# Comm_Log.net
KiCad netlist of a schematic drawn in EAGLE
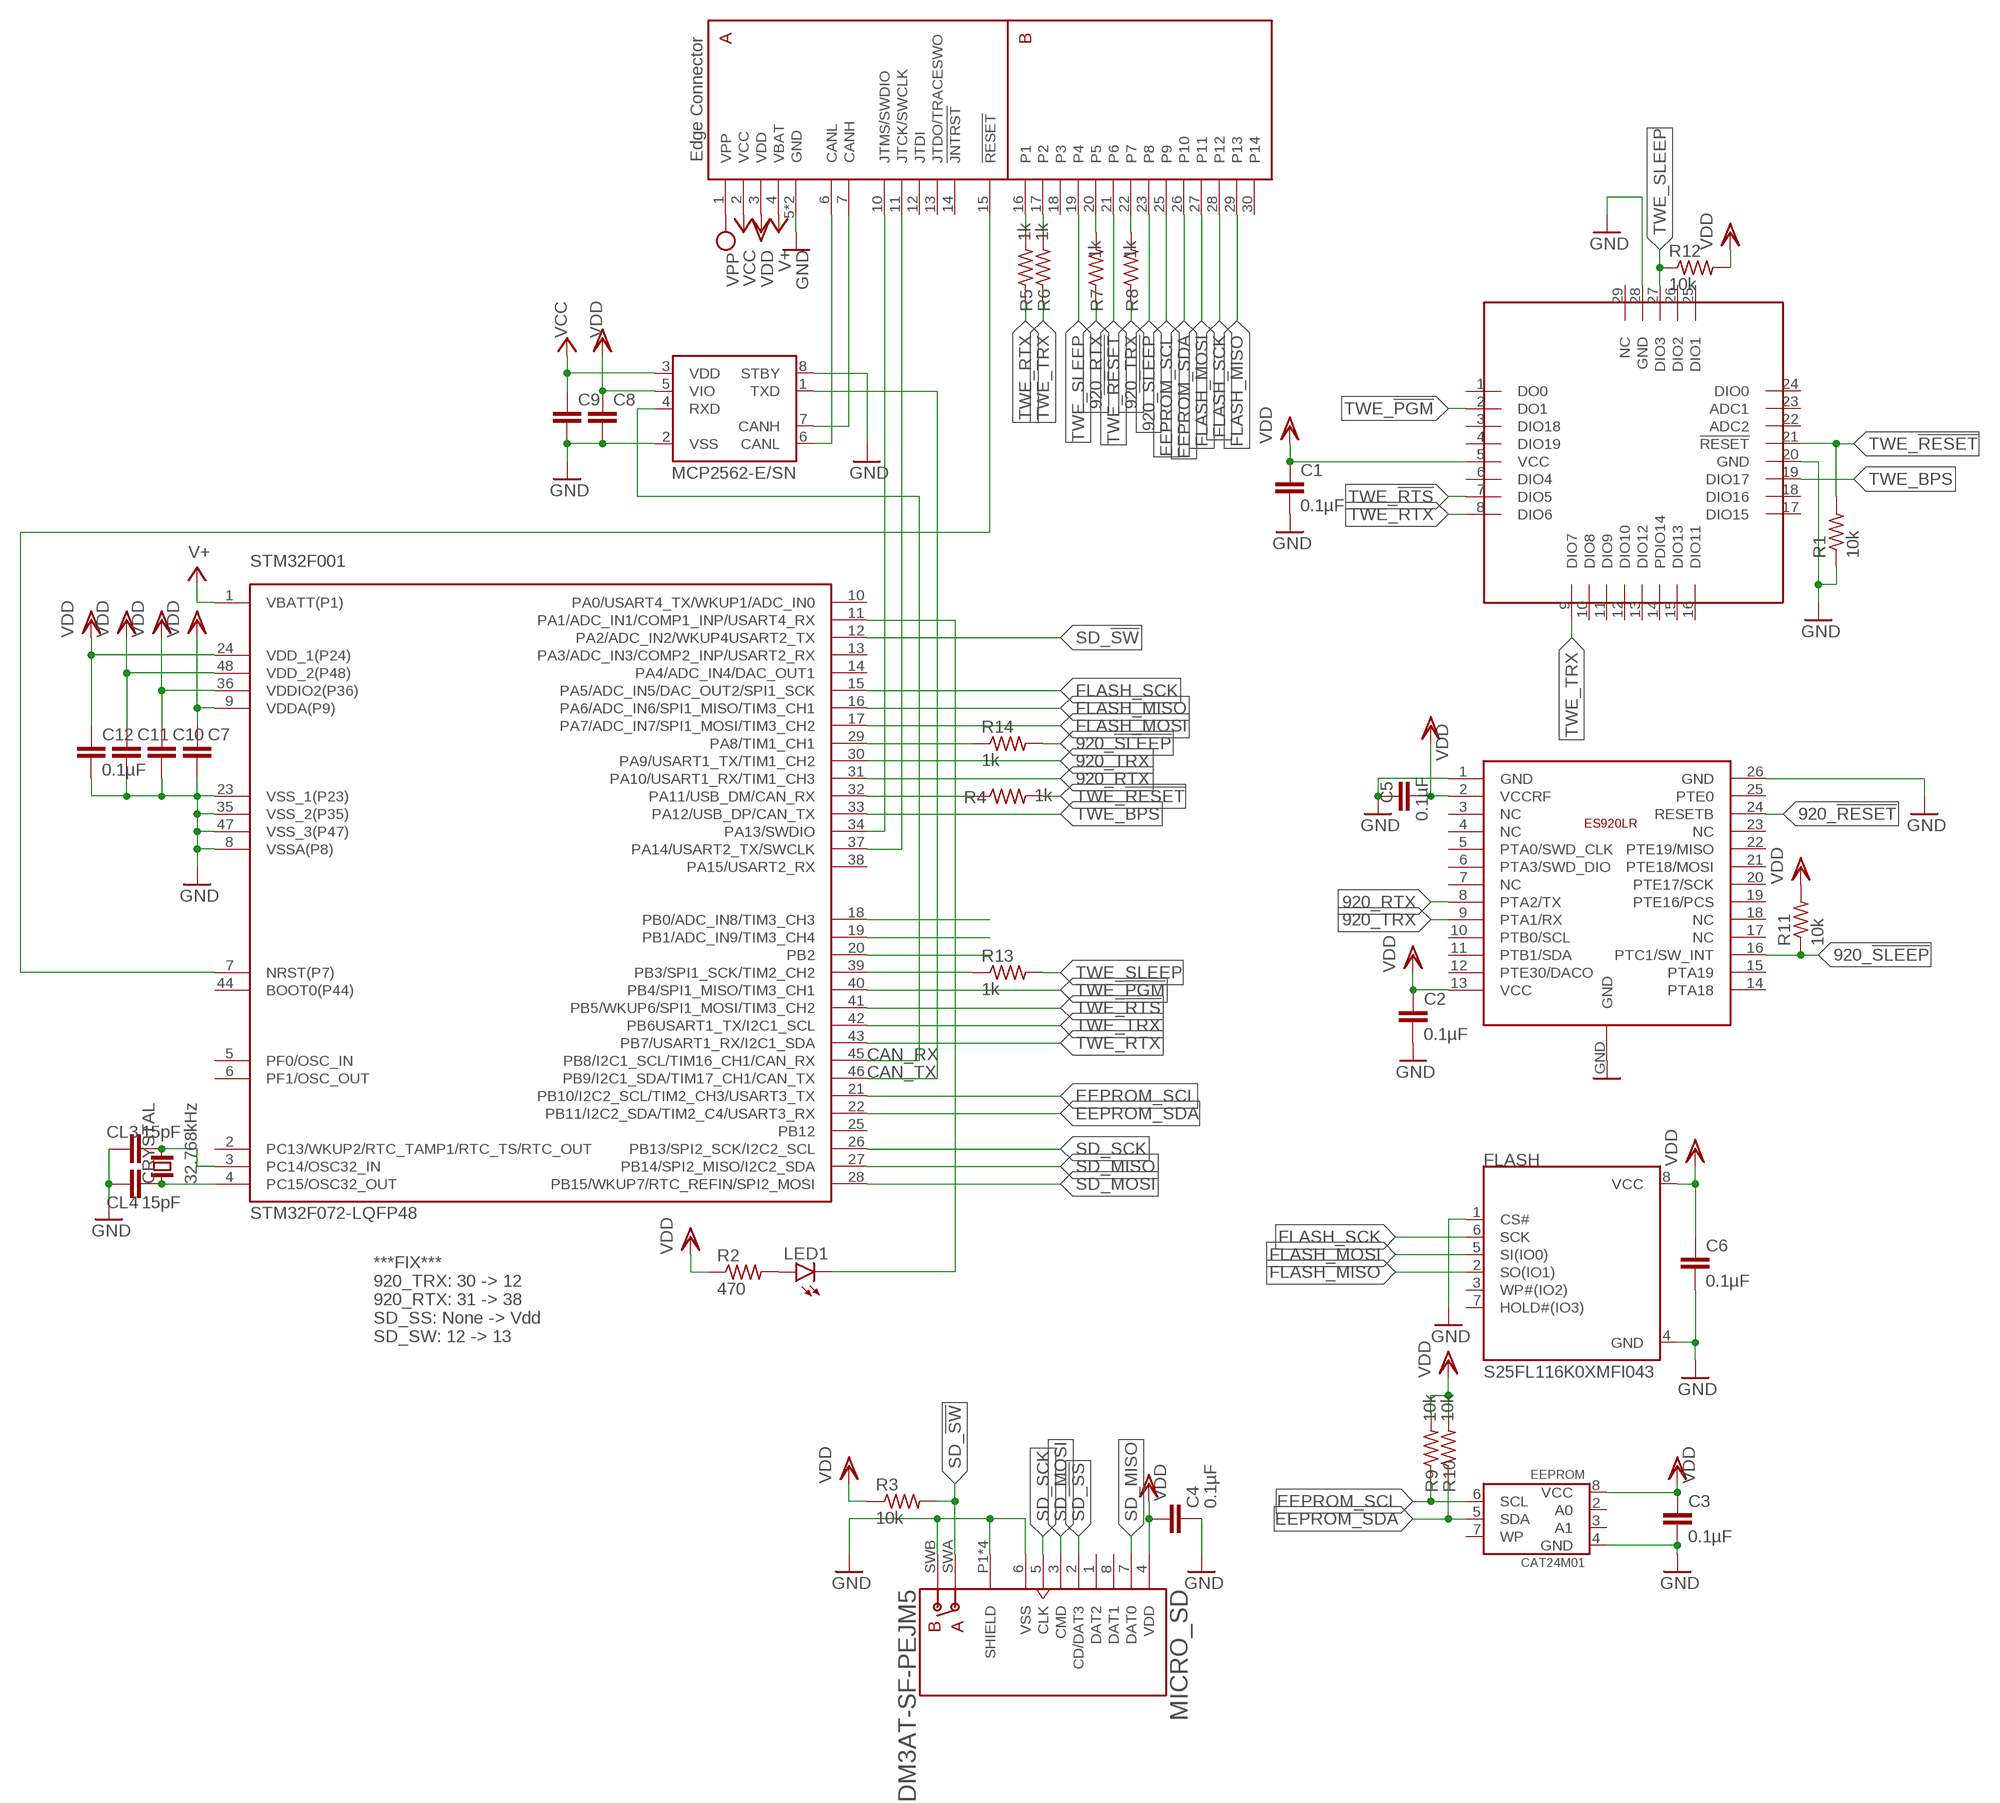
[diagram p0: schematic, sheet 1]

(export (version "E")
  (design (tool "Eeschema 10.0.6"))
  (components
    (comp (ref "C1")
      (value "0.1µF")
      (footprint "eagle-import:C0603K")
      (libsource (lib "eagle-import") (part "C-EUC0603K"))
    )
    (comp (ref "C2")
      (value "0.1µF")
      (footprint "eagle-import:C0603K")
      (libsource (lib "eagle-import") (part "C-EUC0603K"))
    )
    (comp (ref "C3")
      (value "0.1µF")
      (footprint "eagle-import:C0603K")
      (libsource (lib "eagle-import") (part "C-EUC0603K"))
    )
    (comp (ref "C4")
      (value "0.1µF")
      (footprint "eagle-import:C0603K")
      (libsource (lib "eagle-import") (part "C-EUC0603K"))
    )
    (comp (ref "C5")
      (value "0.1µF")
      (footprint "eagle-import:C0603K")
      (libsource (lib "eagle-import") (part "C-EUC0603K"))
    )
    (comp (ref "C6")
      (value "0.1µF")
      (footprint "eagle-import:C0603K")
      (libsource (lib "eagle-import") (part "C-EUC0603K"))
    )
    (comp (ref "C7")
      (value "C-EUC0603K")
      (footprint "eagle-import:C0603K")
      (libsource (lib "eagle-import") (part "C-EUC0603K"))
    )
    (comp (ref "C8")
      (value "C-EUC0603K")
      (footprint "eagle-import:C0603K")
      (libsource (lib "eagle-import") (part "C-EUC0603K"))
    )
    (comp (ref "C9")
      (value "C-EUC0603K")
      (footprint "eagle-import:C0603K")
      (libsource (lib "eagle-import") (part "C-EUC0603K"))
    )
    (comp (ref "C10")
      (value "C-EUC0603K")
      (footprint "eagle-import:C0603K")
      (libsource (lib "eagle-import") (part "C-EUC0603K"))
    )
    (comp (ref "C11")
      (value "C-EUC0603K")
      (footprint "eagle-import:C0603K")
      (libsource (lib "eagle-import") (part "C-EUC0603K"))
    )
    (comp (ref "C12")
      (value "0.1µF")
      (footprint "eagle-import:C0603K")
      (libsource (lib "eagle-import") (part "C-EUC0603K"))
    )
    (comp (ref "CL3")
      (value "15pF")
      (footprint "eagle-import:C0603K")
      (libsource (lib "eagle-import") (part "C-EUC0603K"))
    )
    (comp (ref "CL4")
      (value "15pF")
      (footprint "eagle-import:C0603K")
      (libsource (lib "eagle-import") (part "C-EUC0603K"))
    )
    (comp (ref "CRYSTAL")
      (value "32.768kHz")
      (footprint "eagle-import:FC-255")
      (libsource (lib "eagle-import") (part "CRYTALFC-255"))
    )
    (comp (ref "EEPROM")
      (value "CAT24M01")
      (footprint "eagle-import:SO-8")
      (fields (field (name "MF") "ON Semiconductor"))
      (libsource (lib "eagle-import") (part "CAT24M01"))
    )
    (comp (ref "ES920LR")
      (value "ES920LR")
      (footprint "eagle-import:ES920LR")
      (libsource (lib "eagle-import") (part "ES920LR"))
    )
    (comp (ref "FLASH")
      (value "S25FL116K0XMFI043")
      (footprint "eagle-import:SOIC127P600X175-8N")
      (fields (field (name "MF") "Cypress Semiconductor"))
      (libsource (lib "eagle-import") (part "S25FL116K0XMFI043"))
    )
    (comp (ref "LED1")
      (value "LEDCHIP-LED0603")
      (footprint "eagle-import:CHIP-LED0603")
      (libsource (lib "eagle-import") (part "LEDCHIP-LED0603"))
    )
    (comp (ref "MCP1")
      (value "MCP2562-E/SN")
      (footprint "eagle-import:SOIC127P600X175-8N")
      (fields (field (name "MF") "Microchip"))
      (libsource (lib "eagle-import") (part "MCP2562-E/SN"))
    )
    (comp (ref "MICRO_SD")
      (value "DM3AT-SF-PEJM5")
      (footprint "eagle-import:HRS_DM3AT-SF-PEJM5")
      (fields (field (name "DIGI-KEY_PART_NUMBER") "HR1964CT-ND") (field (name "MF") "Hirose"))
      (libsource (lib "eagle-import") (part "DM3AT-SF-PEJM5"))
    )
    (comp (ref "R1")
      (value "10k")
      (footprint "eagle-import:R0603")
      (libsource (lib "eagle-import") (part "R-US_R0603"))
    )
    (comp (ref "R2")
      (value "470")
      (footprint "eagle-import:R0603")
      (libsource (lib "eagle-import") (part "R-US_R0603"))
    )
    (comp (ref "R3")
      (value "10k")
      (footprint "eagle-import:R0603")
      (libsource (lib "eagle-import") (part "R-US_R0603"))
    )
    (comp (ref "R4")
      (value "1k")
      (footprint "eagle-import:R0603")
      (libsource (lib "eagle-import") (part "R-US_R0603"))
    )
    (comp (ref "R5")
      (value "1k")
      (footprint "eagle-import:R0603")
      (libsource (lib "eagle-import") (part "R-US_R0603"))
    )
    (comp (ref "R6")
      (value "1k")
      (footprint "eagle-import:R0603")
      (libsource (lib "eagle-import") (part "R-US_R0603"))
    )
    (comp (ref "R7")
      (value "1k")
      (footprint "eagle-import:R0603")
      (libsource (lib "eagle-import") (part "R-US_R0603"))
    )
    (comp (ref "R8")
      (value "1k")
      (footprint "eagle-import:R0603")
      (libsource (lib "eagle-import") (part "R-US_R0603"))
    )
    (comp (ref "R9")
      (value "10k")
      (footprint "eagle-import:R0603")
      (libsource (lib "eagle-import") (part "resistor_348_R-US_R0603"))
    )
    (comp (ref "R10")
      (value "10k")
      (footprint "eagle-import:R0603")
      (libsource (lib "eagle-import") (part "resistor_348_R-US_R0603"))
    )
    (comp (ref "R11")
      (value "10k")
      (footprint "eagle-import:R0603")
      (libsource (lib "eagle-import") (part "resistor_348_R-US_R0603"))
    )
    (comp (ref "R12")
      (value "10k")
      (footprint "eagle-import:R0603")
      (libsource (lib "eagle-import") (part "resistor_348_R-US_R0603"))
    )
    (comp (ref "R13")
      (value "1k")
      (footprint "eagle-import:R0603")
      (libsource (lib "eagle-import") (part "resistor_348_R-US_R0603"))
    )
    (comp (ref "R14")
      (value "1k")
      (footprint "eagle-import:R0603")
      (libsource (lib "eagle-import") (part "resistor_348_R-US_R0603"))
    )
    (comp (ref "STM32F001")
      (value "STM32F072-LQFP48")
      (footprint "eagle-import:LQFP48")
      (libsource (lib "eagle-import") (part "STM32F072-LQFP48"))
    )
    (comp (ref "TWE-LITE")
      (value "LITE")
      (footprint "eagle-import:LITE")
      (libsource (lib "eagle-import") (part "LITE"))
    )
    (comp (ref "U$2")
      (value "EDGE30")
      (footprint "eagle-import:EDGE30")
      (libsource (lib "eagle-import") (part "EDGE30"))
    )
  )
  (nets
    (net (code "1") (name "/920_~{RESET}") (class "Default")
      (node (ref "ES920LR") (pin "24") (pinfunction "RESETB_24") (pintype "bidirectional"))
    )
    (net (code "2") (name "/920_~{SLEEP}") (class "Default")
      (node (ref "ES920LR") (pin "16") (pinfunction "PTC1/SW_INT_16") (pintype "bidirectional"))
      (node (ref "R11") (pin "1") (pinfunction "1_1") (pintype "passive"))
      (node (ref "R14") (pin "2") (pinfunction "2_2") (pintype "passive"))
      (node (ref "U$2") (pin "23") (pinfunction "P8_23") (pintype "bidirectional"))
    )
    (net (code "3") (name "/CAN_RX") (class "Default")
      (node (ref "MCP1") (pin "4") (pinfunction "RXD_4") (pintype "output"))
      (node (ref "STM32F001") (pin "45") (pinfunction "PB8/I2C1_SCL/TIM16_CH1/CAN_RX_45") (pintype "bidirectional"))
    )
    (net (code "4") (name "/CAN_TX") (class "Default")
      (node (ref "MCP1") (pin "1") (pinfunction "TXD_1") (pintype "input"))
      (node (ref "STM32F001") (pin "46") (pinfunction "PB9/I2C1_SDA/TIM17_CH1/CAN_TX_46") (pintype "bidirectional"))
    )
    (net (code "5") (name "/SD_~{SS}") (class "Default")
      (node (ref "MICRO_SD") (pin "2") (pinfunction "CD/DAT3_2") (pintype "bidirectional"))
    )
    (net (code "6") (name "/SD_~{SW}") (class "Default")
      (node (ref "MICRO_SD") (pin "SWA") (pinfunction "A_SWA") (pintype "bidirectional"))
      (node (ref "R3") (pin "2") (pinfunction "2_2") (pintype "passive"))
      (node (ref "STM32F001") (pin "12") (pinfunction "PA2/ADC_IN2/WKUP4USART2_TX_12") (pintype "bidirectional"))
    )
    (net (code "7") (name "/TWE_~{PGM}") (class "Default")
      (node (ref "STM32F001") (pin "40") (pinfunction "PB4/SPI1_MISO/TIM3_CH1_40") (pintype "bidirectional"))
      (node (ref "TWE-LITE") (pin "2") (pinfunction "DO1_2") (pintype "bidirectional"))
    )
    (net (code "8") (name "/TWE_~{RESET}") (class "Default")
      (node (ref "R1") (pin "2") (pinfunction "2_2") (pintype "passive"))
      (node (ref "R4") (pin "2") (pinfunction "2_2") (pintype "passive"))
      (node (ref "TWE-LITE") (pin "21") (pinfunction "~{RESET}_21") (pintype "input"))
      (node (ref "U$2") (pin "21") (pinfunction "P6_21") (pintype "bidirectional"))
    )
    (net (code "9") (name "/TWE_~{RTS}") (class "Default")
      (node (ref "STM32F001") (pin "41") (pinfunction "PB5/WKUP6/SPI1_MOSI/TIM3_CH2_41") (pintype "bidirectional"))
      (node (ref "TWE-LITE") (pin "7") (pinfunction "DIO5_7") (pintype "bidirectional"))
    )
    (net (code "10") (name "920_RTX") (class "Default")
      (node (ref "ES920LR") (pin "8") (pinfunction "PTA2/TX_8") (pintype "bidirectional"))
      (node (ref "R7") (pin "1") (pinfunction "1_1") (pintype "passive"))
      (node (ref "STM32F001") (pin "31") (pinfunction "PA10/USART1_RX/TIM1_CH3_31") (pintype "bidirectional"))
    )
    (net (code "11") (name "920_TRX") (class "Default")
      (node (ref "ES920LR") (pin "9") (pinfunction "PTA1/RX_9") (pintype "bidirectional"))
      (node (ref "R8") (pin "1") (pinfunction "1_1") (pintype "passive"))
      (node (ref "STM32F001") (pin "30") (pinfunction "PA9/USART1_TX/TIM1_CH2_30") (pintype "bidirectional"))
    )
    (net (code "12") (name "EEPROM_SCL") (class "Default")
      (node (ref "EEPROM") (pin "6") (pinfunction "SCL_6") (pintype "bidirectional"))
      (node (ref "R9") (pin "1") (pinfunction "1_1") (pintype "passive"))
      (node (ref "STM32F001") (pin "21") (pinfunction "PB10/I2C2_SCL/TIM2_CH3/USART3_TX_21") (pintype "bidirectional"))
      (node (ref "U$2") (pin "25") (pinfunction "P9_25") (pintype "bidirectional"))
    )
    (net (code "13") (name "EEPROM_SDA") (class "Default")
      (node (ref "EEPROM") (pin "5") (pinfunction "SDA_5") (pintype "bidirectional"))
      (node (ref "R10") (pin "1") (pinfunction "1_1") (pintype "passive"))
      (node (ref "STM32F001") (pin "22") (pinfunction "PB11/I2C2_SDA/TIM2_C4/USART3_RX_22") (pintype "bidirectional"))
      (node (ref "U$2") (pin "26") (pinfunction "P10_26") (pintype "bidirectional"))
    )
    (net (code "14") (name "FLASH_MISO") (class "Default")
      (node (ref "FLASH") (pin "2") (pinfunction "SO(IO1)_2") (pintype "bidirectional"))
      (node (ref "STM32F001") (pin "16") (pinfunction "PA6/ADC_IN6/SPI1_MISO/TIM3_CH1_16") (pintype "bidirectional"))
      (node (ref "U$2") (pin "29") (pinfunction "P13_29") (pintype "bidirectional"))
    )
    (net (code "15") (name "FLASH_MOSI") (class "Default")
      (node (ref "FLASH") (pin "5") (pinfunction "SI(IO0)_5") (pintype "bidirectional"))
      (node (ref "STM32F001") (pin "17") (pinfunction "PA7/ADC_IN7/SPI1_MOSI/TIM3_CH2_17") (pintype "bidirectional"))
      (node (ref "U$2") (pin "27") (pinfunction "P11_27") (pintype "bidirectional"))
    )
    (net (code "16") (name "FLASH_SCK") (class "Default")
      (node (ref "FLASH") (pin "6") (pinfunction "SCK_6") (pintype "input"))
      (node (ref "STM32F001") (pin "15") (pinfunction "PA5/ADC_IN5/DAC_OUT2/SPI1_SCK_15") (pintype "bidirectional"))
      (node (ref "U$2") (pin "28") (pinfunction "P12_28") (pintype "bidirectional"))
    )
    (net (code "17") (name "GND") (class "Default")
      (node (ref "C1") (pin "2") (pinfunction "2_2") (pintype "passive"))
      (node (ref "C10") (pin "2") (pinfunction "2_2") (pintype "passive"))
      (node (ref "C11") (pin "2") (pinfunction "2_2") (pintype "passive"))
      (node (ref "C12") (pin "2") (pinfunction "2_2") (pintype "passive"))
      (node (ref "C2") (pin "2") (pinfunction "2_2") (pintype "passive"))
      (node (ref "C3") (pin "2") (pinfunction "2_2") (pintype "passive"))
      (node (ref "C4") (pin "2") (pinfunction "2_2") (pintype "passive"))
      (node (ref "C5") (pin "1") (pinfunction "1_1") (pintype "passive"))
      (node (ref "C6") (pin "2") (pinfunction "2_2") (pintype "passive"))
      (node (ref "C7") (pin "2") (pinfunction "2_2") (pintype "passive"))
      (node (ref "C8") (pin "2") (pinfunction "2_2") (pintype "passive"))
      (node (ref "C9") (pin "2") (pinfunction "2_2") (pintype "passive"))
      (node (ref "CL3") (pin "1") (pinfunction "1_1") (pintype "passive"))
      (node (ref "CL4") (pin "1") (pinfunction "1_1") (pintype "passive"))
      (node (ref "EEPROM") (pin "4") (pinfunction "GND_4") (pintype "bidirectional"))
      (node (ref "ES920LR") (pin "1") (pinfunction "GND_1") (pintype "bidirectional"))
      (node (ref "ES920LR") (pin "26") (pinfunction "GND_26") (pintype "bidirectional"))
      (node (ref "ES920LR") (pin "GND") (pinfunction "GND_GND") (pintype "bidirectional"))
      (node (ref "FLASH") (pin "1") (pinfunction "CS#_1") (pintype "input"))
      (node (ref "FLASH") (pin "4") (pinfunction "GND_4") (pintype "power_in"))
      (node (ref "MCP1") (pin "2") (pinfunction "VSS_2") (pintype "power_in"))
      (node (ref "MCP1") (pin "8") (pinfunction "STBY_8") (pintype "input"))
      (node (ref "MICRO_SD") (pin "6") (pinfunction "VSS_6") (pintype "power_in"))
      (node (ref "MICRO_SD") (pin "P1") (pinfunction "SHIELD_P1") (pintype "passive"))
      (node (ref "MICRO_SD") (pin "P2") (pinfunction "SHIELD_P2") (pintype "passive"))
      (node (ref "MICRO_SD") (pin "P3") (pinfunction "SHIELD_P3") (pintype "passive"))
      (node (ref "MICRO_SD") (pin "P4") (pinfunction "SHIELD_P4") (pintype "passive"))
      (node (ref "MICRO_SD") (pin "SWB") (pinfunction "B_SWB") (pintype "bidirectional"))
      (node (ref "R1") (pin "1") (pinfunction "1_1") (pintype "passive"))
      (node (ref "STM32F001") (pin "23") (pinfunction "VSS_1(P23)_23") (pintype "bidirectional"))
      (node (ref "STM32F001") (pin "35") (pinfunction "VSS_2(P35)_35") (pintype "bidirectional"))
      (node (ref "STM32F001") (pin "47") (pinfunction "VSS_3(P47)_47") (pintype "bidirectional"))
      (node (ref "STM32F001") (pin "8") (pinfunction "VSSA(P8)_8") (pintype "bidirectional"))
      (node (ref "TWE-LITE") (pin "20") (pinfunction "GND_20") (pintype "power_in"))
      (node (ref "TWE-LITE") (pin "28") (pinfunction "GND_28") (pintype "power_in"))
      (node (ref "U$2") (pin "5") (pinfunction "GND_5") (pintype "power_in"))
      (node (ref "U$2") (pin "8") (pinfunction "GND_8") (pintype "power_in"))
    )
    (net (code "18") (name "Net-(LED1-PadA)") (class "Default")
      (node (ref "LED1") (pin "A") (pinfunction "A_A") (pintype "passive"))
      (node (ref "R2") (pin "2") (pinfunction "2_2") (pintype "passive"))
    )
    (net (code "19") (name "Net-(MCP1-CANH)") (class "Default")
      (node (ref "MCP1") (pin "7") (pinfunction "CANH_7") (pintype "input"))
      (node (ref "U$2") (pin "7") (pinfunction "CANH_7") (pintype "bidirectional"))
    )
    (net (code "20") (name "Net-(MCP1-CANL)") (class "Default")
      (node (ref "MCP1") (pin "6") (pinfunction "CANL_6") (pintype "input"))
      (node (ref "U$2") (pin "6") (pinfunction "CANL_6") (pintype "bidirectional"))
    )
    (net (code "21") (name "Net-(STM32F001-NRST(P7))") (class "Default")
      (node (ref "STM32F001") (pin "7") (pinfunction "NRST(P7)_7") (pintype "bidirectional"))
      (node (ref "U$2") (pin "15") (pinfunction "~{RESET}_15") (pintype "bidirectional"))
    )
    (net (code "22") (name "Net-(STM32F001-PA1{slash}ADC_IN1{slash}COMP1_INP{slash}USART4_RX)") (class "Default")
      (node (ref "LED1") (pin "C") (pinfunction "C_C") (pintype "passive"))
      (node (ref "STM32F001") (pin "11") (pinfunction "PA1/ADC_IN1/COMP1_INP/USART4_RX_11") (pintype "bidirectional"))
    )
    (net (code "23") (name "Net-(STM32F001-PA8{slash}TIM1_CH1)") (class "Default")
      (node (ref "R14") (pin "1") (pinfunction "1_1") (pintype "passive"))
      (node (ref "STM32F001") (pin "29") (pinfunction "PA8/TIM1_CH1_29") (pintype "bidirectional"))
    )
    (net (code "24") (name "Net-(STM32F001-PA11{slash}USB_DM{slash}CAN_RX)") (class "Default")
      (node (ref "R4") (pin "1") (pinfunction "1_1") (pintype "passive"))
      (node (ref "STM32F001") (pin "32") (pinfunction "PA11/USB_DM/CAN_RX_32") (pintype "bidirectional"))
    )
    (net (code "25") (name "Net-(STM32F001-PA13{slash}SWDIO)") (class "Default")
      (node (ref "STM32F001") (pin "34") (pinfunction "PA13/SWDIO_34") (pintype "bidirectional"))
      (node (ref "U$2") (pin "10") (pinfunction "JTMS/SWDIO_10") (pintype "bidirectional"))
    )
    (net (code "26") (name "Net-(STM32F001-PA14{slash}USART2_TX{slash}SWCLK)") (class "Default")
      (node (ref "STM32F001") (pin "37") (pinfunction "PA14/USART2_TX/SWCLK_37") (pintype "bidirectional"))
      (node (ref "U$2") (pin "11") (pinfunction "JTCK/SWCLK_11") (pintype "bidirectional"))
    )
    (net (code "27") (name "Net-(STM32F001-PB3{slash}SPI1_SCK{slash}TIM2_CH2)") (class "Default")
      (node (ref "R13") (pin "1") (pinfunction "1_1") (pintype "passive"))
      (node (ref "STM32F001") (pin "39") (pinfunction "PB3/SPI1_SCK/TIM2_CH2_39") (pintype "bidirectional"))
    )
    (net (code "28") (name "Net-(STM32F001-PC14{slash}OSC32_IN)") (class "Default")
      (node (ref "CL3") (pin "2") (pinfunction "2_2") (pintype "passive"))
      (node (ref "CRYSTAL") (pin "2") (pinfunction "2_2") (pintype "passive"))
      (node (ref "STM32F001") (pin "3") (pinfunction "PC14/OSC32_IN_3") (pintype "bidirectional"))
    )
    (net (code "29") (name "Net-(STM32F001-PC15{slash}OSC32_OUT)") (class "Default")
      (node (ref "CL4") (pin "2") (pinfunction "2_2") (pintype "passive"))
      (node (ref "CRYSTAL") (pin "1") (pinfunction "1_1") (pintype "passive"))
      (node (ref "STM32F001") (pin "4") (pinfunction "PC15/OSC32_OUT_4") (pintype "bidirectional"))
    )
    (net (code "30") (name "Net-(U$2-P1)") (class "Default")
      (node (ref "R5") (pin "2") (pinfunction "2_2") (pintype "passive"))
      (node (ref "U$2") (pin "16") (pinfunction "P1_16") (pintype "bidirectional"))
    )
    (net (code "31") (name "Net-(U$2-P2)") (class "Default")
      (node (ref "R6") (pin "2") (pinfunction "2_2") (pintype "passive"))
      (node (ref "U$2") (pin "17") (pinfunction "P2_17") (pintype "bidirectional"))
    )
    (net (code "32") (name "Net-(U$2-P5)") (class "Default")
      (node (ref "R7") (pin "2") (pinfunction "2_2") (pintype "passive"))
      (node (ref "U$2") (pin "20") (pinfunction "P5_20") (pintype "bidirectional"))
    )
    (net (code "33") (name "Net-(U$2-P7)") (class "Default")
      (node (ref "R8") (pin "2") (pinfunction "2_2") (pintype "passive"))
      (node (ref "U$2") (pin "22") (pinfunction "P7_22") (pintype "bidirectional"))
    )
    (net (code "34") (name "SD_MISO") (class "Default")
      (node (ref "MICRO_SD") (pin "7") (pinfunction "DAT0_7") (pintype "bidirectional"))
      (node (ref "STM32F001") (pin "27") (pinfunction "PB14/SPI2_MISO/I2C2_SDA_27") (pintype "bidirectional"))
    )
    (net (code "35") (name "SD_MOSI") (class "Default")
      (node (ref "MICRO_SD") (pin "3") (pinfunction "CMD_3") (pintype "bidirectional"))
      (node (ref "STM32F001") (pin "28") (pinfunction "PB15/WKUP7/RTC_REFIN/SPI2_MOSI_28") (pintype "bidirectional"))
    )
    (net (code "36") (name "SD_SCK") (class "Default")
      (node (ref "MICRO_SD") (pin "5") (pinfunction "CLK_5") (pintype "bidirectional"))
      (node (ref "STM32F001") (pin "26") (pinfunction "PB13/SPI2_SCK/I2C2_SCL_26") (pintype "bidirectional"))
    )
    (net (code "37") (name "TWE_BPS") (class "Default")
      (node (ref "STM32F001") (pin "33") (pinfunction "PA12/USB_DP/CAN_TX_33") (pintype "bidirectional"))
      (node (ref "TWE-LITE") (pin "19") (pinfunction "DIO17_19") (pintype "bidirectional"))
    )
    (net (code "38") (name "TWE_RTX") (class "Default")
      (node (ref "R5") (pin "1") (pinfunction "1_1") (pintype "passive"))
      (node (ref "STM32F001") (pin "43") (pinfunction "PB7/USART1_RX/I2C1_SDA_43") (pintype "bidirectional"))
      (node (ref "TWE-LITE") (pin "8") (pinfunction "DIO6_8") (pintype "bidirectional"))
    )
    (net (code "39") (name "TWE_SLEEP") (class "Default")
      (node (ref "R12") (pin "1") (pinfunction "1_1") (pintype "passive"))
      (node (ref "R13") (pin "2") (pinfunction "2_2") (pintype "passive"))
      (node (ref "TWE-LITE") (pin "27") (pinfunction "DIO3_27") (pintype "bidirectional"))
      (node (ref "U$2") (pin "19") (pinfunction "P4_19") (pintype "bidirectional"))
    )
    (net (code "40") (name "TWE_TRX") (class "Default")
      (node (ref "R6") (pin "1") (pinfunction "1_1") (pintype "passive"))
      (node (ref "STM32F001") (pin "42") (pinfunction "PB6USART1_TX/I2C1_SCL_42") (pintype "bidirectional"))
      (node (ref "TWE-LITE") (pin "9") (pinfunction "DIO7_9") (pintype "bidirectional"))
    )
    (net (code "41") (name "V+") (class "Default")
      (node (ref "STM32F001") (pin "1") (pinfunction "VBATT(P1)_1") (pintype "bidirectional"))
      (node (ref "U$2") (pin "4") (pinfunction "VBAT_4") (pintype "power_in"))
    )
    (net (code "42") (name "VCC") (class "Default")
      (node (ref "C9") (pin "1") (pinfunction "1_1") (pintype "passive"))
      (node (ref "MCP1") (pin "3") (pinfunction "VDD_3") (pintype "power_in"))
      (node (ref "U$2") (pin "2") (pinfunction "VCC_2") (pintype "power_in"))
    )
    (net (code "43") (name "VDD") (class "Default")
      (node (ref "C1") (pin "1") (pinfunction "1_1") (pintype "passive"))
      (node (ref "C10") (pin "1") (pinfunction "1_1") (pintype "passive"))
      (node (ref "C11") (pin "1") (pinfunction "1_1") (pintype "passive"))
      (node (ref "C12") (pin "1") (pinfunction "1_1") (pintype "passive"))
      (node (ref "C2") (pin "1") (pinfunction "1_1") (pintype "passive"))
      (node (ref "C3") (pin "1") (pinfunction "1_1") (pintype "passive"))
      (node (ref "C4") (pin "1") (pinfunction "1_1") (pintype "passive"))
      (node (ref "C5") (pin "2") (pinfunction "2_2") (pintype "passive"))
      (node (ref "C6") (pin "1") (pinfunction "1_1") (pintype "passive"))
      (node (ref "C7") (pin "1") (pinfunction "1_1") (pintype "passive"))
      (node (ref "C8") (pin "1") (pinfunction "1_1") (pintype "passive"))
      (node (ref "EEPROM") (pin "8") (pinfunction "VCC_8") (pintype "bidirectional"))
      (node (ref "ES920LR") (pin "13") (pinfunction "VCC_13") (pintype "bidirectional"))
      (node (ref "ES920LR") (pin "2") (pinfunction "VCCRF_2") (pintype "bidirectional"))
      (node (ref "FLASH") (pin "8") (pinfunction "VCC_8") (pintype "power_in"))
      (node (ref "MCP1") (pin "5") (pinfunction "VIO_5") (pintype "power_in"))
      (node (ref "MICRO_SD") (pin "4") (pinfunction "VDD_4") (pintype "power_in"))
      (node (ref "R10") (pin "2") (pinfunction "2_2") (pintype "passive"))
      (node (ref "R11") (pin "2") (pinfunction "2_2") (pintype "passive"))
      (node (ref "R12") (pin "2") (pinfunction "2_2") (pintype "passive"))
      (node (ref "R2") (pin "1") (pinfunction "1_1") (pintype "passive"))
      (node (ref "R3") (pin "1") (pinfunction "1_1") (pintype "passive"))
      (node (ref "R9") (pin "2") (pinfunction "2_2") (pintype "passive"))
      (node (ref "STM32F001") (pin "24") (pinfunction "VDD_1(P24)_24") (pintype "bidirectional"))
      (node (ref "STM32F001") (pin "36") (pinfunction "VDDIO2(P36)_36") (pintype "bidirectional"))
      (node (ref "STM32F001") (pin "48") (pinfunction "VDD_2(P48)_48") (pintype "bidirectional"))
      (node (ref "STM32F001") (pin "9") (pinfunction "VDDA(P9)_9") (pintype "bidirectional"))
      (node (ref "TWE-LITE") (pin "5") (pinfunction "VCC_5") (pintype "power_in"))
      (node (ref "U$2") (pin "3") (pinfunction "VDD_3") (pintype "power_in"))
    )
    (net (code "44") (name "VPP") (class "Default")
      (node (ref "U$2") (pin "1") (pinfunction "VPP_1") (pintype "power_in"))
    )
    (net (code "45") (name "unconnected-(EEPROM-A0-Pad2)") (class "Default")
      (node (ref "EEPROM") (pin "2") (pinfunction "A0_2") (pintype "bidirectional"))
    )
    (net (code "46") (name "unconnected-(EEPROM-A1-Pad3)") (class "Default")
      (node (ref "EEPROM") (pin "3") (pinfunction "A1_3") (pintype "bidirectional"))
    )
    (net (code "47") (name "unconnected-(EEPROM-WP-Pad7)") (class "Default")
      (node (ref "EEPROM") (pin "7") (pinfunction "WP_7") (pintype "bidirectional"))
    )
    (net (code "48") (name "unconnected-(ES920LR-NC-Pad3)") (class "Default")
      (node (ref "ES920LR") (pin "3") (pinfunction "NC_3") (pintype "bidirectional"))
    )
    (net (code "49") (name "unconnected-(ES920LR-NC-Pad4)") (class "Default")
      (node (ref "ES920LR") (pin "4") (pinfunction "NC_4") (pintype "bidirectional"))
    )
    (net (code "50") (name "unconnected-(ES920LR-NC-Pad7)") (class "Default")
      (node (ref "ES920LR") (pin "7") (pinfunction "NC_7") (pintype "bidirectional"))
    )
    (net (code "51") (name "unconnected-(ES920LR-NC-Pad17)") (class "Default")
      (node (ref "ES920LR") (pin "17") (pinfunction "NC_17") (pintype "bidirectional"))
    )
    (net (code "52") (name "unconnected-(ES920LR-NC-Pad18)") (class "Default")
      (node (ref "ES920LR") (pin "18") (pinfunction "NC_18") (pintype "bidirectional"))
    )
    (net (code "53") (name "unconnected-(ES920LR-NC-Pad23)") (class "Default")
      (node (ref "ES920LR") (pin "23") (pinfunction "NC_23") (pintype "bidirectional"))
    )
    (net (code "54") (name "unconnected-(ES920LR-PTA0{slash}SWD_CLK-Pad5)") (class "Default")
      (node (ref "ES920LR") (pin "5") (pinfunction "PTA0/SWD_CLK_5") (pintype "bidirectional"))
    )
    (net (code "55") (name "unconnected-(ES920LR-PTA3{slash}SWD_DIO-Pad6)") (class "Default")
      (node (ref "ES920LR") (pin "6") (pinfunction "PTA3/SWD_DIO_6") (pintype "bidirectional"))
    )
    (net (code "56") (name "unconnected-(ES920LR-PTA18-Pad14)") (class "Default")
      (node (ref "ES920LR") (pin "14") (pinfunction "PTA18_14") (pintype "bidirectional"))
    )
    (net (code "57") (name "unconnected-(ES920LR-PTA19-Pad15)") (class "Default")
      (node (ref "ES920LR") (pin "15") (pinfunction "PTA19_15") (pintype "bidirectional"))
    )
    (net (code "58") (name "unconnected-(ES920LR-PTB0{slash}SCL-Pad10)") (class "Default")
      (node (ref "ES920LR") (pin "10") (pinfunction "PTB0/SCL_10") (pintype "bidirectional"))
    )
    (net (code "59") (name "unconnected-(ES920LR-PTB1{slash}SDA-Pad11)") (class "Default")
      (node (ref "ES920LR") (pin "11") (pinfunction "PTB1/SDA_11") (pintype "bidirectional"))
    )
    (net (code "60") (name "unconnected-(ES920LR-PTE0-Pad25)") (class "Default")
      (node (ref "ES920LR") (pin "25") (pinfunction "PTE0_25") (pintype "bidirectional"))
    )
    (net (code "61") (name "unconnected-(ES920LR-PTE16{slash}PCS-Pad19)") (class "Default")
      (node (ref "ES920LR") (pin "19") (pinfunction "PTE16/PCS_19") (pintype "bidirectional"))
    )
    (net (code "62") (name "unconnected-(ES920LR-PTE17{slash}SCK-Pad20)") (class "Default")
      (node (ref "ES920LR") (pin "20") (pinfunction "PTE17/SCK_20") (pintype "bidirectional"))
    )
    (net (code "63") (name "unconnected-(ES920LR-PTE18{slash}MOSI-Pad21)") (class "Default")
      (node (ref "ES920LR") (pin "21") (pinfunction "PTE18/MOSI_21") (pintype "bidirectional"))
    )
    (net (code "64") (name "unconnected-(ES920LR-PTE19{slash}MISO-Pad22)") (class "Default")
      (node (ref "ES920LR") (pin "22") (pinfunction "PTE19/MISO_22") (pintype "bidirectional"))
    )
    (net (code "65") (name "unconnected-(ES920LR-PTE30{slash}DACO-Pad12)") (class "Default")
      (node (ref "ES920LR") (pin "12") (pinfunction "PTE30/DACO_12") (pintype "bidirectional"))
    )
    (net (code "66") (name "unconnected-(FLASH-HOLD#(IO3)-Pad7)") (class "Default")
      (node (ref "FLASH") (pin "7") (pinfunction "HOLD#(IO3)_7") (pintype "bidirectional"))
    )
    (net (code "67") (name "unconnected-(FLASH-WP#(IO2)-Pad3)") (class "Default")
      (node (ref "FLASH") (pin "3") (pinfunction "WP#(IO2)_3") (pintype "bidirectional"))
    )
    (net (code "68") (name "unconnected-(MICRO_SD-DAT1-Pad8)") (class "Default")
      (node (ref "MICRO_SD") (pin "8") (pinfunction "DAT1_8") (pintype "bidirectional"))
    )
    (net (code "69") (name "unconnected-(MICRO_SD-DAT2-Pad1)") (class "Default")
      (node (ref "MICRO_SD") (pin "1") (pinfunction "DAT2_1") (pintype "bidirectional"))
    )
    (net (code "70") (name "unconnected-(STM32F001-BOOT0(P44)-Pad44)") (class "Default")
      (node (ref "STM32F001") (pin "44") (pinfunction "BOOT0(P44)_44") (pintype "bidirectional"))
    )
    (net (code "71") (name "unconnected-(STM32F001-PA0{slash}USART4_TX{slash}WKUP1{slash}ADC_IN0-Pad10)") (class "Default")
      (node (ref "STM32F001") (pin "10") (pinfunction "PA0/USART4_TX/WKUP1/ADC_IN0_10") (pintype "bidirectional"))
    )
    (net (code "72") (name "unconnected-(STM32F001-PA3{slash}ADC_IN3{slash}COMP2_INP{slash}USART2_RX-Pad13)") (class "Default")
      (node (ref "STM32F001") (pin "13") (pinfunction "PA3/ADC_IN3/COMP2_INP/USART2_RX_13") (pintype "bidirectional"))
    )
    (net (code "73") (name "unconnected-(STM32F001-PA4{slash}ADC_IN4{slash}DAC_OUT1-Pad14)") (class "Default")
      (node (ref "STM32F001") (pin "14") (pinfunction "PA4/ADC_IN4/DAC_OUT1_14") (pintype "bidirectional"))
    )
    (net (code "74") (name "unconnected-(STM32F001-PA15{slash}USART2_RX-Pad38)") (class "Default")
      (node (ref "STM32F001") (pin "38") (pinfunction "PA15/USART2_RX_38") (pintype "bidirectional"))
    )
    (net (code "75") (name "unconnected-(STM32F001-PB0{slash}ADC_IN8{slash}TIM3_CH3-Pad18)") (class "Default")
      (node (ref "STM32F001") (pin "18") (pinfunction "PB0/ADC_IN8/TIM3_CH3_18") (pintype "bidirectional"))
    )
    (net (code "76") (name "unconnected-(STM32F001-PB1{slash}ADC_IN9{slash}TIM3_CH4-Pad19)") (class "Default")
      (node (ref "STM32F001") (pin "19") (pinfunction "PB1/ADC_IN9/TIM3_CH4_19") (pintype "bidirectional"))
    )
    (net (code "77") (name "unconnected-(STM32F001-PB2-Pad20)") (class "Default")
      (node (ref "STM32F001") (pin "20") (pinfunction "PB2_20") (pintype "bidirectional"))
    )
    (net (code "78") (name "unconnected-(STM32F001-PB12-Pad25)") (class "Default")
      (node (ref "STM32F001") (pin "25") (pinfunction "PB12_25") (pintype "bidirectional"))
    )
    (net (code "79") (name "unconnected-(STM32F001-PC13{slash}WKUP2{slash}RTC_TAMP1{slash}RTC_TS{slash}RTC_OUT-Pad2)") (class "Default")
      (node (ref "STM32F001") (pin "2") (pinfunction "PC13/WKUP2/RTC_TAMP1/RTC_TS/RTC_OUT_2") (pintype "bidirectional"))
    )
    (net (code "80") (name "unconnected-(STM32F001-PF0{slash}OSC_IN-Pad5)") (class "Default")
      (node (ref "STM32F001") (pin "5") (pinfunction "PF0/OSC_IN_5") (pintype "bidirectional"))
    )
    (net (code "81") (name "unconnected-(STM32F001-PF1{slash}OSC_OUT-Pad6)") (class "Default")
      (node (ref "STM32F001") (pin "6") (pinfunction "PF1/OSC_OUT_6") (pintype "bidirectional"))
    )
    (net (code "82") (name "unconnected-(TWE-LITE-ADC1-Pad23)") (class "Default")
      (node (ref "TWE-LITE") (pin "23") (pinfunction "ADC1_23") (pintype "bidirectional"))
    )
    (net (code "83") (name "unconnected-(TWE-LITE-ADC2-Pad22)") (class "Default")
      (node (ref "TWE-LITE") (pin "22") (pinfunction "ADC2_22") (pintype "bidirectional"))
    )
    (net (code "84") (name "unconnected-(TWE-LITE-DIO0-Pad24)") (class "Default")
      (node (ref "TWE-LITE") (pin "24") (pinfunction "DIO0_24") (pintype "bidirectional"))
    )
    (net (code "85") (name "unconnected-(TWE-LITE-DIO1-Pad25)") (class "Default")
      (node (ref "TWE-LITE") (pin "25") (pinfunction "DIO1_25") (pintype "bidirectional"))
    )
    (net (code "86") (name "unconnected-(TWE-LITE-DIO2-Pad26)") (class "Default")
      (node (ref "TWE-LITE") (pin "26") (pinfunction "DIO2_26") (pintype "bidirectional"))
    )
    (net (code "87") (name "unconnected-(TWE-LITE-DIO4-Pad6)") (class "Default")
      (node (ref "TWE-LITE") (pin "6") (pinfunction "DIO4_6") (pintype "bidirectional"))
    )
    (net (code "88") (name "unconnected-(TWE-LITE-DIO8-Pad10)") (class "Default")
      (node (ref "TWE-LITE") (pin "10") (pinfunction "DIO8_10") (pintype "bidirectional"))
    )
    (net (code "89") (name "unconnected-(TWE-LITE-DIO9-Pad11)") (class "Default")
      (node (ref "TWE-LITE") (pin "11") (pinfunction "DIO9_11") (pintype "bidirectional"))
    )
    (net (code "90") (name "unconnected-(TWE-LITE-DIO10-Pad12)") (class "Default")
      (node (ref "TWE-LITE") (pin "12") (pinfunction "DIO10_12") (pintype "bidirectional"))
    )
    (net (code "91") (name "unconnected-(TWE-LITE-DIO11-Pad16)") (class "Default")
      (node (ref "TWE-LITE") (pin "16") (pinfunction "DIO11_16") (pintype "bidirectional"))
    )
    (net (code "92") (name "unconnected-(TWE-LITE-DIO12-Pad13)") (class "Default")
      (node (ref "TWE-LITE") (pin "13") (pinfunction "DIO12_13") (pintype "bidirectional"))
    )
    (net (code "93") (name "unconnected-(TWE-LITE-DIO13-Pad15)") (class "Default")
      (node (ref "TWE-LITE") (pin "15") (pinfunction "DIO13_15") (pintype "bidirectional"))
    )
    (net (code "94") (name "unconnected-(TWE-LITE-DIO15-Pad17)") (class "Default")
      (node (ref "TWE-LITE") (pin "17") (pinfunction "DIO15_17") (pintype "bidirectional"))
    )
    (net (code "95") (name "unconnected-(TWE-LITE-DIO16-Pad18)") (class "Default")
      (node (ref "TWE-LITE") (pin "18") (pinfunction "DIO16_18") (pintype "bidirectional"))
    )
    (net (code "96") (name "unconnected-(TWE-LITE-DIO18-Pad3)") (class "Default")
      (node (ref "TWE-LITE") (pin "3") (pinfunction "DIO18_3") (pintype "bidirectional"))
    )
    (net (code "97") (name "unconnected-(TWE-LITE-DIO19-Pad4)") (class "Default")
      (node (ref "TWE-LITE") (pin "4") (pinfunction "DIO19_4") (pintype "bidirectional"))
    )
    (net (code "98") (name "unconnected-(TWE-LITE-DO0-Pad1)") (class "Default")
      (node (ref "TWE-LITE") (pin "1") (pinfunction "DO0_1") (pintype "output"))
    )
    (net (code "99") (name "unconnected-(TWE-LITE-NC-Pad29)") (class "Default")
      (node (ref "TWE-LITE") (pin "29") (pinfunction "NC_29") (pintype "no_connect"))
    )
    (net (code "100") (name "unconnected-(TWE-LITE-PDIO14-Pad14)") (class "Default")
      (node (ref "TWE-LITE") (pin "14") (pinfunction "PDIO14_14") (pintype "bidirectional"))
    )
    (net (code "101") (name "unconnected-(U$2-JTDI-Pad12)") (class "Default")
      (node (ref "U$2") (pin "12") (pinfunction "JTDI_12") (pintype "bidirectional"))
    )
    (net (code "102") (name "unconnected-(U$2-JTDO{slash}TRACESWO-Pad13)") (class "Default")
      (node (ref "U$2") (pin "13") (pinfunction "JTDO/TRACESWO_13") (pintype "bidirectional"))
    )
    (net (code "103") (name "unconnected-(U$2-P3-Pad18)") (class "Default")
      (node (ref "U$2") (pin "18") (pinfunction "P3_18") (pintype "bidirectional"))
    )
    (net (code "104") (name "unconnected-(U$2-P14-Pad30)") (class "Default")
      (node (ref "U$2") (pin "30") (pinfunction "P14_30") (pintype "bidirectional"))
    )
    (net (code "105") (name "unconnected-(U$2-~{JNTRST}-Pad14)") (class "Default")
      (node (ref "U$2") (pin "14") (pinfunction "~{JNTRST}_14") (pintype "bidirectional"))
    )
  )
)
